# LV.net
KiCad netlist of a schematic drawn in Altium Designer
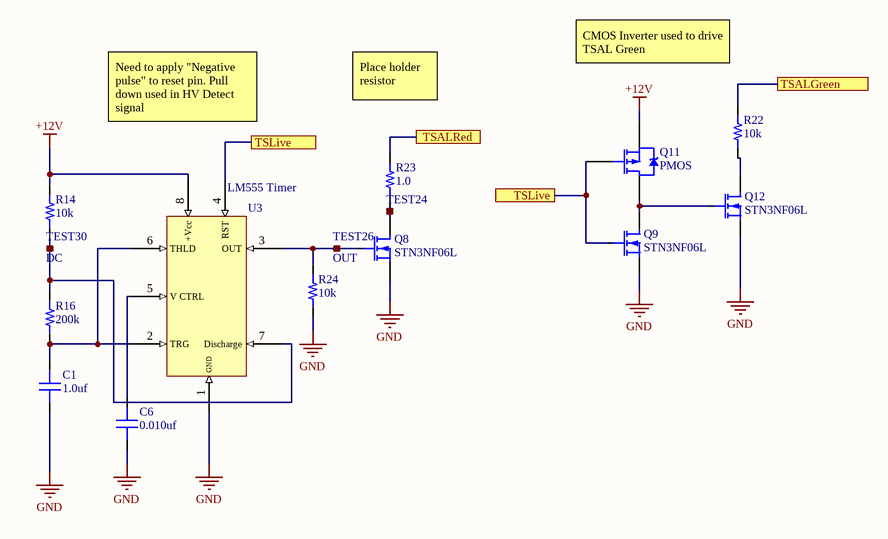
[diagram p0: LV.SchDoc]

(export (version "E")
  (design (tool "Eeschema 10.0.6"))
  (components
    (comp (ref "C1")
      (value "1.0uf")
      (footprint "CAP 0603/1608")
      (fields
        (field (name "Comment") "Capacitor MLCC 1.0uf 16V CAP 0603/1608")
        (field (name "CREATED_BY") "Nick Mah")
      )
      (libsource (lib "Altium-Lib") (part "Capacitor"))
    )
    (comp (ref "C6")
      (value "0.010uf")
      (footprint "CAP 0402/1005")
      (fields
        (field (name "Comment") "Capacitor MLCC 0.010uf 16V CAP 0402/1005")
        (field (name "CREATED_BY") "Nick Mah")
      )
      (libsource (lib "Altium-Lib") (part "Capacitor"))
    )
    (comp (ref "Q8")
      (value "STN3NF06L")
      (footprint "STN3NF06L")
      (description "MOSFET N-CH 60V 4A SOT223")
      (fields (field (name "CREATED_BY") "Graydon"))
      (libsource (lib "Altium-Lib") (part "STN3NF06L"))
    )
    (comp (ref "Q9")
      (value "STN3NF06L")
      (footprint "STN3NF06L")
      (description "MOSFET N-CH 60V 4A SOT223")
      (fields (field (name "CREATED_BY") "Graydon"))
      (libsource (lib "Altium-Lib") (part "STN3NF06L"))
    )
    (comp (ref "Q11")
      (value "PMOS")
      (footprint "SOT-23 (TO-236)")
      (description "P-Channel 60V 170mA (Ta) 360mW (Ta) Surface Mount SOT-23-3")
      (fields (field (name "MFRPARTNO") "BSS84PH6327XTSA2") (field (name "CREATED_BY") "Angel"))
      (libsource (lib "Altium-Lib") (part "BSS84PH6327XTSA2"))
    )
    (comp (ref "Q12")
      (value "STN3NF06L")
      (footprint "STN3NF06L")
      (description "MOSFET N-CH 60V 4A SOT223")
      (fields (field (name "CREATED_BY") "Graydon"))
      (libsource (lib "Altium-Lib") (part "STN3NF06L"))
    )
    (comp (ref "R14")
      (value "10k")
      (footprint "RES 0402/1005")
      (fields
        (field (name "TOLERANCE") "1%")
        (field (name "POWER") "1/10W")
        (field (name "Comment") "Resistor 1.1 0402 1/10W 1%")
        (field (name "CREATED_BY") "Nick Mah")
      )
      (libsource (lib "Altium-Lib") (part "Resistor"))
    )
    (comp (ref "R16")
      (value "200k")
      (footprint "RES 0603/1608")
      (fields
        (field (name "TOLERANCE") "1%")
        (field (name "POWER") "1/10W")
        (field (name "Comment") "Resistor 200k 0603 1/10W 1%")
        (field (name "CREATED_BY") "Nick Mah")
      )
      (libsource (lib "Altium-Lib") (part "Resistor"))
    )
    (comp (ref "R22")
      (value "10k")
      (footprint "RES 0402/1005")
      (fields
        (field (name "TOLERANCE") "1%")
        (field (name "POWER") "1/10W")
        (field (name "Comment") "Resistor 10k 0402 1/10W 1%")
        (field (name "CREATED_BY") "Nick Mah")
      )
      (libsource (lib "Altium-Lib") (part "Resistor"))
    )
    (comp (ref "R23")
      (value "1.0")
      (footprint "RES 0603/1608")
      (fields
        (field (name "TOLERANCE") "1%")
        (field (name "POWER") "1/10W")
        (field (name "Comment") "Resistor 1.0 0603 1/10W 1%")
        (field (name "CREATED_BY") "Nick Mah")
      )
      (libsource (lib "Altium-Lib") (part "Resistor"))
    )
    (comp (ref "R24")
      (value "10k")
      (footprint "RES 0402/1005")
      (fields
        (field (name "TOLERANCE") "1%")
        (field (name "POWER") "1/10W")
        (field (name "Comment") "Resistor 10k 0402 1/10W 1%")
        (field (name "CREATED_BY") "Nick Mah")
      )
      (libsource (lib "Altium-Lib") (part "Resistor"))
    )
    (comp (ref "TEST24")
      (value "~")
      (footprint "RCU-0C")
      (description "Test point")
      (fields
        (field (name "MFRPARTNO") "RCU-0C")
        (field (name "CREATED_BY") "Graydon")
        (field (name "UPDATED_BY") "Null")
      )
      (libsource (lib "Altium-Lib") (part "RCU-0C"))
    )
    (comp (ref "TEST26")
      (value "OUT")
      (footprint "RCU-0C")
      (description "Test point")
      (fields
        (field (name "MFRPARTNO") "RCU-0C")
        (field (name "CREATED_BY") "Graydon")
        (field (name "UPDATED_BY") "Null")
      )
      (libsource (lib "Altium-Lib") (part "RCU-0C"))
    )
    (comp (ref "TEST30")
      (value "DC")
      (footprint "RCU-0C")
      (description "Test point")
      (fields
        (field (name "MFRPARTNO") "RCU-0C")
        (field (name "CREATED_BY") "Graydon")
        (field (name "UPDATED_BY") "Null")
      )
      (libsource (lib "Altium-Lib") (part "RCU-0C"))
    )
    (comp (ref "U3")
      (value "LM555 Timer")
      (footprint "SOIC-8")
      (libsource (lib "Altium-Lib") (part "LM555 Timer"))
    )
  )
  (nets
    (net (code "1") (name "+12V") (class "Default")
      (node (ref "Q11") (pin "2") (pinfunction "S_2") (pintype "passive"))
      (node (ref "R14") (pin "2") (pinfunction "2_2") (pintype "passive"))
      (node (ref "U3") (pin "8") (pinfunction "+Vcc_8") (pintype "input"))
    )
    (net (code "2") (name "/TSALGreen") (class "Default")
      (node (ref "R22") (pin "2") (pinfunction "2_2") (pintype "passive"))
    )
    (net (code "3") (name "/TSALRed") (class "Default")
      (node (ref "R23") (pin "2") (pinfunction "2_2") (pintype "passive"))
    )
    (net (code "4") (name "/TSLive") (class "Default")
      (node (ref "Q11") (pin "1") (pinfunction "G_1") (pintype "passive"))
      (node (ref "Q9") (pin "1") (pinfunction "G_1") (pintype "passive"))
      (node (ref "U3") (pin "4") (pinfunction "RST_4") (pintype "input"))
    )
    (net (code "5") (name "GND") (class "Default")
      (node (ref "C1") (pin "1") (pinfunction "1_1") (pintype "passive"))
      (node (ref "C6") (pin "1") (pinfunction "1_1") (pintype "passive"))
      (node (ref "Q12") (pin "3") (pinfunction "S_3") (pintype "passive"))
      (node (ref "Q8") (pin "3") (pinfunction "S_3") (pintype "passive"))
      (node (ref "Q9") (pin "3") (pinfunction "S_3") (pintype "passive"))
      (node (ref "R24") (pin "1") (pinfunction "1_1") (pintype "passive"))
      (node (ref "U3") (pin "1") (pinfunction "GND_1") (pintype "input"))
    )
    (net (code "6") (name "Net-(Q8-D)") (class "Default")
      (node (ref "Q8") (pin "2") (pinfunction "D_2") (pintype "passive"))
      (node (ref "R23") (pin "1") (pinfunction "1_1") (pintype "passive"))
      (node (ref "TEST24") (pin "1") (pintype "passive"))
    )
    (net (code "7") (name "Net-(Q8-G)") (class "Default")
      (node (ref "Q8") (pin "1") (pinfunction "G_1") (pintype "passive"))
      (node (ref "R24") (pin "2") (pinfunction "2_2") (pintype "passive"))
      (node (ref "TEST26") (pin "1") (pintype "passive"))
      (node (ref "U3") (pin "3") (pinfunction "OUT_3") (pintype "input"))
    )
    (net (code "8") (name "Net-(Q11-D)") (class "Default")
      (node (ref "Q11") (pin "3") (pinfunction "D_3") (pintype "passive"))
      (node (ref "Q12") (pin "1") (pinfunction "G_1") (pintype "passive"))
      (node (ref "Q9") (pin "2") (pinfunction "D_2") (pintype "passive"))
    )
    (net (code "9") (name "Net-(Q12-D)") (class "Default")
      (node (ref "Q12") (pin "2") (pinfunction "D_2") (pintype "passive"))
      (node (ref "R22") (pin "1") (pinfunction "1_1") (pintype "passive"))
    )
    (net (code "10") (name "Net-(U3-Discharge)") (class "Default")
      (node (ref "R14") (pin "1") (pinfunction "1_1") (pintype "passive"))
      (node (ref "R16") (pin "2") (pinfunction "2_2") (pintype "passive"))
      (node (ref "TEST30") (pin "1") (pintype "passive"))
      (node (ref "U3") (pin "7") (pinfunction "Discharge_7") (pintype "input"))
    )
    (net (code "11") (name "Net-(U3-THLD)") (class "Default")
      (node (ref "C1") (pin "2") (pinfunction "2_2") (pintype "passive"))
      (node (ref "R16") (pin "1") (pinfunction "1_1") (pintype "passive"))
      (node (ref "U3") (pin "2") (pinfunction "TRG_2") (pintype "input"))
      (node (ref "U3") (pin "6") (pinfunction "THLD_6") (pintype "input"))
    )
    (net (code "12") (name "Net-(U3-V_CTRL)") (class "Default")
      (node (ref "C6") (pin "2") (pinfunction "2_2") (pintype "passive"))
      (node (ref "U3") (pin "5") (pinfunction "V_CTRL_5") (pintype "input"))
    )
  )
)
